# FLK01A.net
KiCad netlist of a schematic drawn in EAGLE
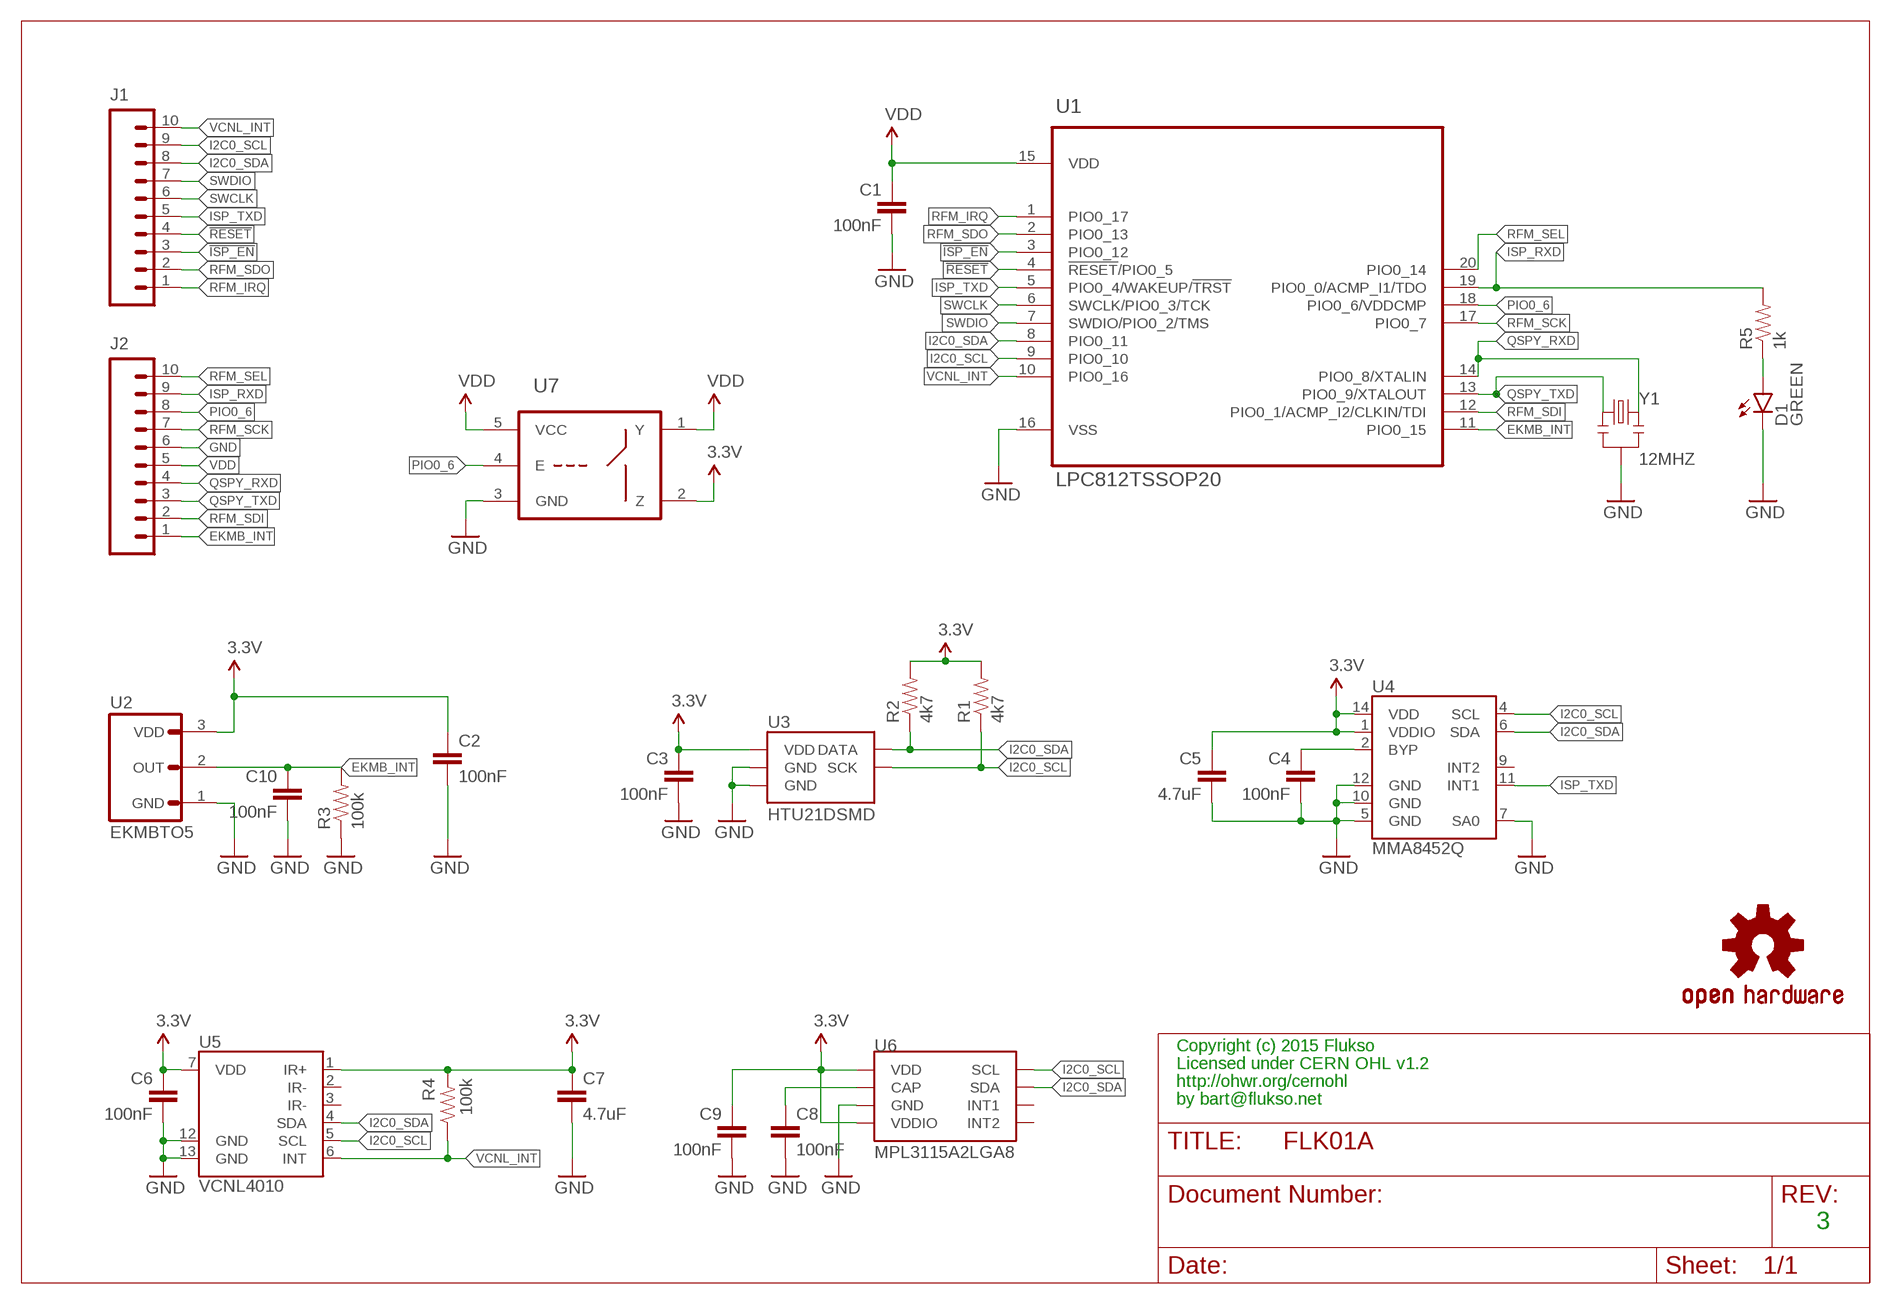
[diagram p0: schematic, sheet 1]

(export (version "E")
  (design (tool "Eeschema 10.0.6"))
  (components
    (comp (ref "C1")
      (value "100nF")
      (footprint "eagle-import:0402-CAP")
      (libsource (lib "eagle-import") (part "CAP0402-CAP"))
    )
    (comp (ref "C2")
      (value "100nF")
      (footprint "eagle-import:0402-CAP")
      (libsource (lib "eagle-import") (part "CAP0402-CAP"))
    )
    (comp (ref "C3")
      (value "100nF")
      (footprint "eagle-import:0402-CAP")
      (libsource (lib "eagle-import") (part "CAP0402-CAP"))
    )
    (comp (ref "C4")
      (value "100nF")
      (footprint "eagle-import:0402-CAP")
      (libsource (lib "eagle-import") (part "CAP0402-CAP"))
    )
    (comp (ref "C5")
      (value "4.7uF")
      (footprint "eagle-import:C0805K")
      (libsource (lib "eagle-import") (part "CAP0805-CAP"))
    )
    (comp (ref "C6")
      (value "100nF")
      (footprint "eagle-import:0402-CAP")
      (libsource (lib "eagle-import") (part "CAP0402-CAP"))
    )
    (comp (ref "C7")
      (value "4.7uF")
      (footprint "eagle-import:C0805K")
      (libsource (lib "eagle-import") (part "CAP0805-CAP"))
    )
    (comp (ref "C8")
      (value "100nF")
      (footprint "eagle-import:0402-CAP")
      (libsource (lib "eagle-import") (part "CAP0402-CAP"))
    )
    (comp (ref "C9")
      (value "100nF")
      (footprint "eagle-import:0402-CAP")
      (libsource (lib "eagle-import") (part "CAP0402-CAP"))
    )
    (comp (ref "C10")
      (value "100nF")
      (footprint "eagle-import:0402-CAP")
      (libsource (lib "eagle-import") (part "CAP0402-CAP"))
    )
    (comp (ref "D1")
      (value "GREEN")
      (footprint "eagle-import:LED-0603")
      (libsource (lib "eagle-import") (part "LED-GREEN0603"))
    )
    (comp (ref "J1")
      (value "M10SMD_MALE_SHORT")
      (footprint "eagle-import:1X10_SMD_MALE_SHORT")
      (libsource (lib "eagle-import") (part "M10SMD_MALE_SHORT"))
    )
    (comp (ref "J2")
      (value "M10SMD_MALE_SHORT")
      (footprint "eagle-import:1X10_SMD_MALE_SHORT")
      (libsource (lib "eagle-import") (part "M10SMD_MALE_SHORT"))
    )
    (comp (ref "R1")
      (value "4k7")
      (footprint "eagle-import:0402-RES")
      (libsource (lib "eagle-import") (part "RESISTOR0402-RES"))
    )
    (comp (ref "R2")
      (value "4k7")
      (footprint "eagle-import:0402-RES")
      (libsource (lib "eagle-import") (part "RESISTOR0402-RES"))
    )
    (comp (ref "R3")
      (value "100k")
      (footprint "eagle-import:0402-RES")
      (libsource (lib "eagle-import") (part "RESISTOR0402-RES"))
    )
    (comp (ref "R4")
      (value "100k")
      (footprint "eagle-import:0402-RES")
      (libsource (lib "eagle-import") (part "RESISTOR0402-RES"))
    )
    (comp (ref "R5")
      (value "1k")
      (footprint "eagle-import:0402-RES")
      (libsource (lib "eagle-import") (part "RESISTOR0402-RES"))
    )
    (comp (ref "U$1")
      (value "OSHW-LOGOS")
      (footprint "eagle-import:OSHW-LOGO-S")
      (libsource (lib "eagle-import") (part "OSHW-LOGOS"))
    )
    (comp (ref "U1")
      (value "LPC812TSSOP20")
      (footprint "eagle-import:TSSOP20")
      (libsource (lib "eagle-import") (part "LPC812TSSOP20"))
    )
    (comp (ref "U2")
      (value "EKMBTO5")
      (footprint "eagle-import:TO5")
      (libsource (lib "eagle-import") (part "EKMBTO5"))
    )
    (comp (ref "U3")
      (value "HTU21DSMD")
      (footprint "eagle-import:HTU21D")
      (libsource (lib "eagle-import") (part "HTU21DSMD"))
    )
    (comp (ref "U4")
      (value "MMA8452Q")
      (footprint "eagle-import:QFN-16_0.5MM")
      (libsource (lib "eagle-import") (part "MMA8452Q"))
    )
    (comp (ref "U5")
      (value "VCNL4010")
      (footprint "eagle-import:VCNL4010")
      (libsource (lib "eagle-import") (part "VCNL4010"))
    )
    (comp (ref "U6")
      (value "MPL3115A2LGA8")
      (footprint "eagle-import:LGA8")
      (libsource (lib "eagle-import") (part "MPL3115A2LGA8"))
    )
    (comp (ref "U7")
      (value "741G66")
      (footprint "eagle-import:SOT353")
      (libsource (lib "eagle-import") (part "741G66"))
    )
    (comp (ref "Y1")
      (value "12MHZ")
      (footprint "eagle-import:RESONATOR-SMD")
      (libsource (lib "eagle-import") (part "RESONATOR8MHZ"))
    )
  )
  (nets
    (net (code "1") (name "/~{ISP_EN}") (class "Default")
      (node (ref "J1") (pin "3") (pinfunction "3_3") (pintype "passive"))
      (node (ref "U1") (pin "3") (pinfunction "PIO0_12_3") (pintype "bidirectional"))
    )
    (net (code "2") (name "/~{RESET}") (class "Default")
      (node (ref "J1") (pin "4") (pinfunction "4_4") (pintype "passive"))
      (node (ref "U1") (pin "4") (pinfunction "~{RESET}/PIO0_5_4") (pintype "bidirectional"))
    )
    (net (code "3") (name "3.3V") (class "Default")
      (node (ref "C2") (pin "1") (pinfunction "1_1") (pintype "passive"))
      (node (ref "C3") (pin "1") (pinfunction "1_1") (pintype "passive"))
      (node (ref "C5") (pin "1") (pinfunction "1_1") (pintype "passive"))
      (node (ref "C6") (pin "1") (pinfunction "1_1") (pintype "passive"))
      (node (ref "C7") (pin "1") (pinfunction "1_1") (pintype "passive"))
      (node (ref "C9") (pin "1") (pinfunction "1_1") (pintype "passive"))
      (node (ref "R1") (pin "2") (pinfunction "2_2") (pintype "passive"))
      (node (ref "R2") (pin "2") (pinfunction "2_2") (pintype "passive"))
      (node (ref "R4") (pin "2") (pinfunction "2_2") (pintype "passive"))
      (node (ref "U2") (pin "3") (pinfunction "VDD_3") (pintype "power_in"))
      (node (ref "U3") (pin "VDD") (pinfunction "VDD_VDD") (pintype "power_in"))
      (node (ref "U4") (pin "1") (pinfunction "VDDIO_1") (pintype "bidirectional"))
      (node (ref "U4") (pin "14") (pinfunction "VDD_14") (pintype "bidirectional"))
      (node (ref "U5") (pin "1") (pinfunction "IR+_1") (pintype "bidirectional"))
      (node (ref "U5") (pin "7") (pinfunction "VDD_7") (pintype "bidirectional"))
      (node (ref "U6") (pin "1") (pinfunction "VDD_1") (pintype "power_in"))
      (node (ref "U6") (pin "4") (pinfunction "VDDIO_4") (pintype "power_in"))
      (node (ref "U7") (pin "2") (pinfunction "Z_2") (pintype "bidirectional"))
    )
    (net (code "4") (name "EKMB_INT") (class "Default")
      (node (ref "C10") (pin "1") (pinfunction "1_1") (pintype "passive"))
      (node (ref "J2") (pin "1") (pinfunction "1_1") (pintype "passive"))
      (node (ref "R3") (pin "2") (pinfunction "2_2") (pintype "passive"))
      (node (ref "U1") (pin "11") (pinfunction "PIO0_15_11") (pintype "bidirectional"))
      (node (ref "U2") (pin "2") (pinfunction "OUT_2") (pintype "output"))
    )
    (net (code "5") (name "GND") (class "Default")
      (node (ref "C1") (pin "2") (pinfunction "2_2") (pintype "passive"))
      (node (ref "C10") (pin "2") (pinfunction "2_2") (pintype "passive"))
      (node (ref "C2") (pin "2") (pinfunction "2_2") (pintype "passive"))
      (node (ref "C3") (pin "2") (pinfunction "2_2") (pintype "passive"))
      (node (ref "C4") (pin "2") (pinfunction "2_2") (pintype "passive"))
      (node (ref "C5") (pin "2") (pinfunction "2_2") (pintype "passive"))
      (node (ref "C6") (pin "2") (pinfunction "2_2") (pintype "passive"))
      (node (ref "C7") (pin "2") (pinfunction "2_2") (pintype "passive"))
      (node (ref "C8") (pin "2") (pinfunction "2_2") (pintype "passive"))
      (node (ref "C9") (pin "2") (pinfunction "2_2") (pintype "passive"))
      (node (ref "D1") (pin "C") (pinfunction "C_C") (pintype "passive"))
      (node (ref "J2") (pin "6") (pinfunction "6_6") (pintype "passive"))
      (node (ref "R3") (pin "1") (pinfunction "1_1") (pintype "passive"))
      (node (ref "U1") (pin "16") (pinfunction "VSS_16") (pintype "power_in"))
      (node (ref "U2") (pin "1") (pinfunction "GND_1") (pintype "power_in"))
      (node (ref "U3") (pin "7") (pinfunction "GND_7") (pintype "power_in"))
      (node (ref "U3") (pin "GND") (pinfunction "GND_GND") (pintype "power_in"))
      (node (ref "U4") (pin "10") (pinfunction "GND_10") (pintype "bidirectional"))
      (node (ref "U4") (pin "12") (pinfunction "GND_12") (pintype "bidirectional"))
      (node (ref "U4") (pin "5") (pinfunction "GND_5") (pintype "bidirectional"))
      (node (ref "U4") (pin "7") (pinfunction "SA0_7") (pintype "bidirectional"))
      (node (ref "U5") (pin "12") (pinfunction "GND_12") (pintype "bidirectional"))
      (node (ref "U5") (pin "13") (pinfunction "GND_13") (pintype "bidirectional"))
      (node (ref "U6") (pin "3") (pinfunction "GND_3") (pintype "power_in"))
      (node (ref "U7") (pin "3") (pinfunction "GND_3") (pintype "passive"))
      (node (ref "Y1") (pin "2") (pinfunction "2_2") (pintype "passive"))
    )
    (net (code "6") (name "I2C0_SCL") (class "Default")
      (node (ref "J1") (pin "9") (pinfunction "9_9") (pintype "passive"))
      (node (ref "R1") (pin "1") (pinfunction "1_1") (pintype "passive"))
      (node (ref "U1") (pin "9") (pinfunction "PIO0_10_9") (pintype "input"))
      (node (ref "U3") (pin "SCK") (pinfunction "SCK_SCK") (pintype "input"))
      (node (ref "U4") (pin "4") (pinfunction "SCL_4") (pintype "bidirectional"))
      (node (ref "U5") (pin "5") (pinfunction "SCL_5") (pintype "bidirectional"))
      (node (ref "U6") (pin "8") (pinfunction "SCL_8") (pintype "bidirectional"))
    )
    (net (code "7") (name "I2C0_SDA") (class "Default")
      (node (ref "J1") (pin "8") (pinfunction "8_8") (pintype "passive"))
      (node (ref "R2") (pin "1") (pinfunction "1_1") (pintype "passive"))
      (node (ref "U1") (pin "8") (pinfunction "PIO0_11_8") (pintype "input"))
      (node (ref "U3") (pin "DATA") (pinfunction "DATA_DATA") (pintype "bidirectional"))
      (node (ref "U4") (pin "6") (pinfunction "SDA_6") (pintype "bidirectional"))
      (node (ref "U5") (pin "4") (pinfunction "SDA_4") (pintype "bidirectional"))
      (node (ref "U6") (pin "7") (pinfunction "SDA_7") (pintype "bidirectional"))
    )
    (net (code "8") (name "ISP_RXD") (class "Default")
      (node (ref "J2") (pin "9") (pinfunction "9_9") (pintype "passive"))
      (node (ref "R5") (pin "2") (pinfunction "2_2") (pintype "passive"))
      (node (ref "U1") (pin "19") (pinfunction "PIO0_0/ACMP_I1/TDO_19") (pintype "bidirectional"))
    )
    (net (code "9") (name "ISP_TXD") (class "Default")
      (node (ref "J1") (pin "5") (pinfunction "5_5") (pintype "passive"))
      (node (ref "U1") (pin "5") (pinfunction "PIO0_4/WAKEUP/~{TRST}_5") (pintype "bidirectional"))
      (node (ref "U4") (pin "11") (pinfunction "INT1_11") (pintype "bidirectional"))
    )
    (net (code "10") (name "Net-(D1-PadA)") (class "Default")
      (node (ref "D1") (pin "A") (pinfunction "A_A") (pintype "passive"))
      (node (ref "R5") (pin "1") (pinfunction "1_1") (pintype "passive"))
    )
    (net (code "11") (name "Net-(U4-BYP)") (class "Default")
      (node (ref "C4") (pin "1") (pinfunction "1_1") (pintype "passive"))
      (node (ref "U4") (pin "2") (pinfunction "BYP_2") (pintype "bidirectional"))
    )
    (net (code "12") (name "Net-(U6-CAP)") (class "Default")
      (node (ref "C8") (pin "1") (pinfunction "1_1") (pintype "passive"))
      (node (ref "U6") (pin "2") (pinfunction "CAP_2") (pintype "power_in"))
    )
    (net (code "13") (name "PIO0_6") (class "Default")
      (node (ref "J2") (pin "8") (pinfunction "8_8") (pintype "passive"))
      (node (ref "U1") (pin "18") (pinfunction "PIO0_6/VDDCMP_18") (pintype "bidirectional"))
      (node (ref "U7") (pin "4") (pinfunction "E_4") (pintype "input"))
    )
    (net (code "14") (name "QSPY_RXD") (class "Default")
      (node (ref "J2") (pin "4") (pinfunction "4_4") (pintype "passive"))
      (node (ref "U1") (pin "14") (pinfunction "PIO0_8/XTALIN_14") (pintype "bidirectional"))
      (node (ref "Y1") (pin "3") (pinfunction "3_3") (pintype "passive"))
    )
    (net (code "15") (name "QSPY_TXD") (class "Default")
      (node (ref "J2") (pin "3") (pinfunction "3_3") (pintype "passive"))
      (node (ref "U1") (pin "13") (pinfunction "PIO0_9/XTALOUT_13") (pintype "bidirectional"))
      (node (ref "Y1") (pin "1") (pinfunction "1_1") (pintype "passive"))
    )
    (net (code "16") (name "RFM_IRQ") (class "Default")
      (node (ref "J1") (pin "1") (pinfunction "1_1") (pintype "passive"))
      (node (ref "U1") (pin "1") (pinfunction "PIO0_17_1") (pintype "bidirectional"))
    )
    (net (code "17") (name "RFM_SCK") (class "Default")
      (node (ref "J2") (pin "7") (pinfunction "7_7") (pintype "passive"))
      (node (ref "U1") (pin "17") (pinfunction "PIO0_7_17") (pintype "bidirectional"))
    )
    (net (code "18") (name "RFM_SDI") (class "Default")
      (node (ref "J2") (pin "2") (pinfunction "2_2") (pintype "passive"))
      (node (ref "U1") (pin "12") (pinfunction "PIO0_1/ACMP_I2/CLKIN/TDI_12") (pintype "bidirectional"))
    )
    (net (code "19") (name "RFM_SDO") (class "Default")
      (node (ref "J1") (pin "2") (pinfunction "2_2") (pintype "passive"))
      (node (ref "U1") (pin "2") (pinfunction "PIO0_13_2") (pintype "bidirectional"))
    )
    (net (code "20") (name "RFM_SEL") (class "Default")
      (node (ref "J2") (pin "10") (pinfunction "10_10") (pintype "passive"))
      (node (ref "U1") (pin "20") (pinfunction "PIO0_14_20") (pintype "bidirectional"))
    )
    (net (code "21") (name "SWCLK") (class "Default")
      (node (ref "J1") (pin "6") (pinfunction "6_6") (pintype "passive"))
      (node (ref "U1") (pin "6") (pinfunction "SWCLK/PIO0_3/TCK_6") (pintype "bidirectional"))
    )
    (net (code "22") (name "SWDIO") (class "Default")
      (node (ref "J1") (pin "7") (pinfunction "7_7") (pintype "passive"))
      (node (ref "U1") (pin "7") (pinfunction "SWDIO/PIO0_2/TMS_7") (pintype "bidirectional"))
    )
    (net (code "23") (name "VCNL_INT") (class "Default")
      (node (ref "J1") (pin "10") (pinfunction "10_10") (pintype "passive"))
      (node (ref "R4") (pin "1") (pinfunction "1_1") (pintype "passive"))
      (node (ref "U1") (pin "10") (pinfunction "PIO0_16_10") (pintype "bidirectional"))
      (node (ref "U5") (pin "6") (pinfunction "INT_6") (pintype "bidirectional"))
    )
    (net (code "24") (name "VDD") (class "Default")
      (node (ref "C1") (pin "1") (pinfunction "1_1") (pintype "passive"))
      (node (ref "J2") (pin "5") (pinfunction "5_5") (pintype "passive"))
      (node (ref "U1") (pin "15") (pinfunction "VDD_15") (pintype "power_in"))
      (node (ref "U7") (pin "1") (pinfunction "Y_1") (pintype "bidirectional"))
      (node (ref "U7") (pin "5") (pinfunction "VCC_5") (pintype "power_in"))
    )
    (net (code "25") (name "unconnected-(U4-INT2-Pad9)") (class "Default")
      (node (ref "U4") (pin "9") (pinfunction "INT2_9") (pintype "bidirectional"))
    )
    (net (code "26") (name "unconnected-(U5-IR--Pad2)") (class "Default")
      (node (ref "U5") (pin "2") (pinfunction "IR-_2") (pintype "bidirectional"))
    )
    (net (code "27") (name "unconnected-(U5-IR--Pad3)") (class "Default")
      (node (ref "U5") (pin "3") (pinfunction "IR-_3") (pintype "bidirectional"))
    )
    (net (code "28") (name "unconnected-(U6-INT1-Pad6)") (class "Default")
      (node (ref "U6") (pin "6") (pinfunction "INT1_6") (pintype "output"))
    )
    (net (code "29") (name "unconnected-(U6-INT2-Pad5)") (class "Default")
      (node (ref "U6") (pin "5") (pinfunction "INT2_5") (pintype "output"))
    )
  )
)
